# power_input_SCH1.net
KiCad netlist of a schematic drawn in Altium Designer
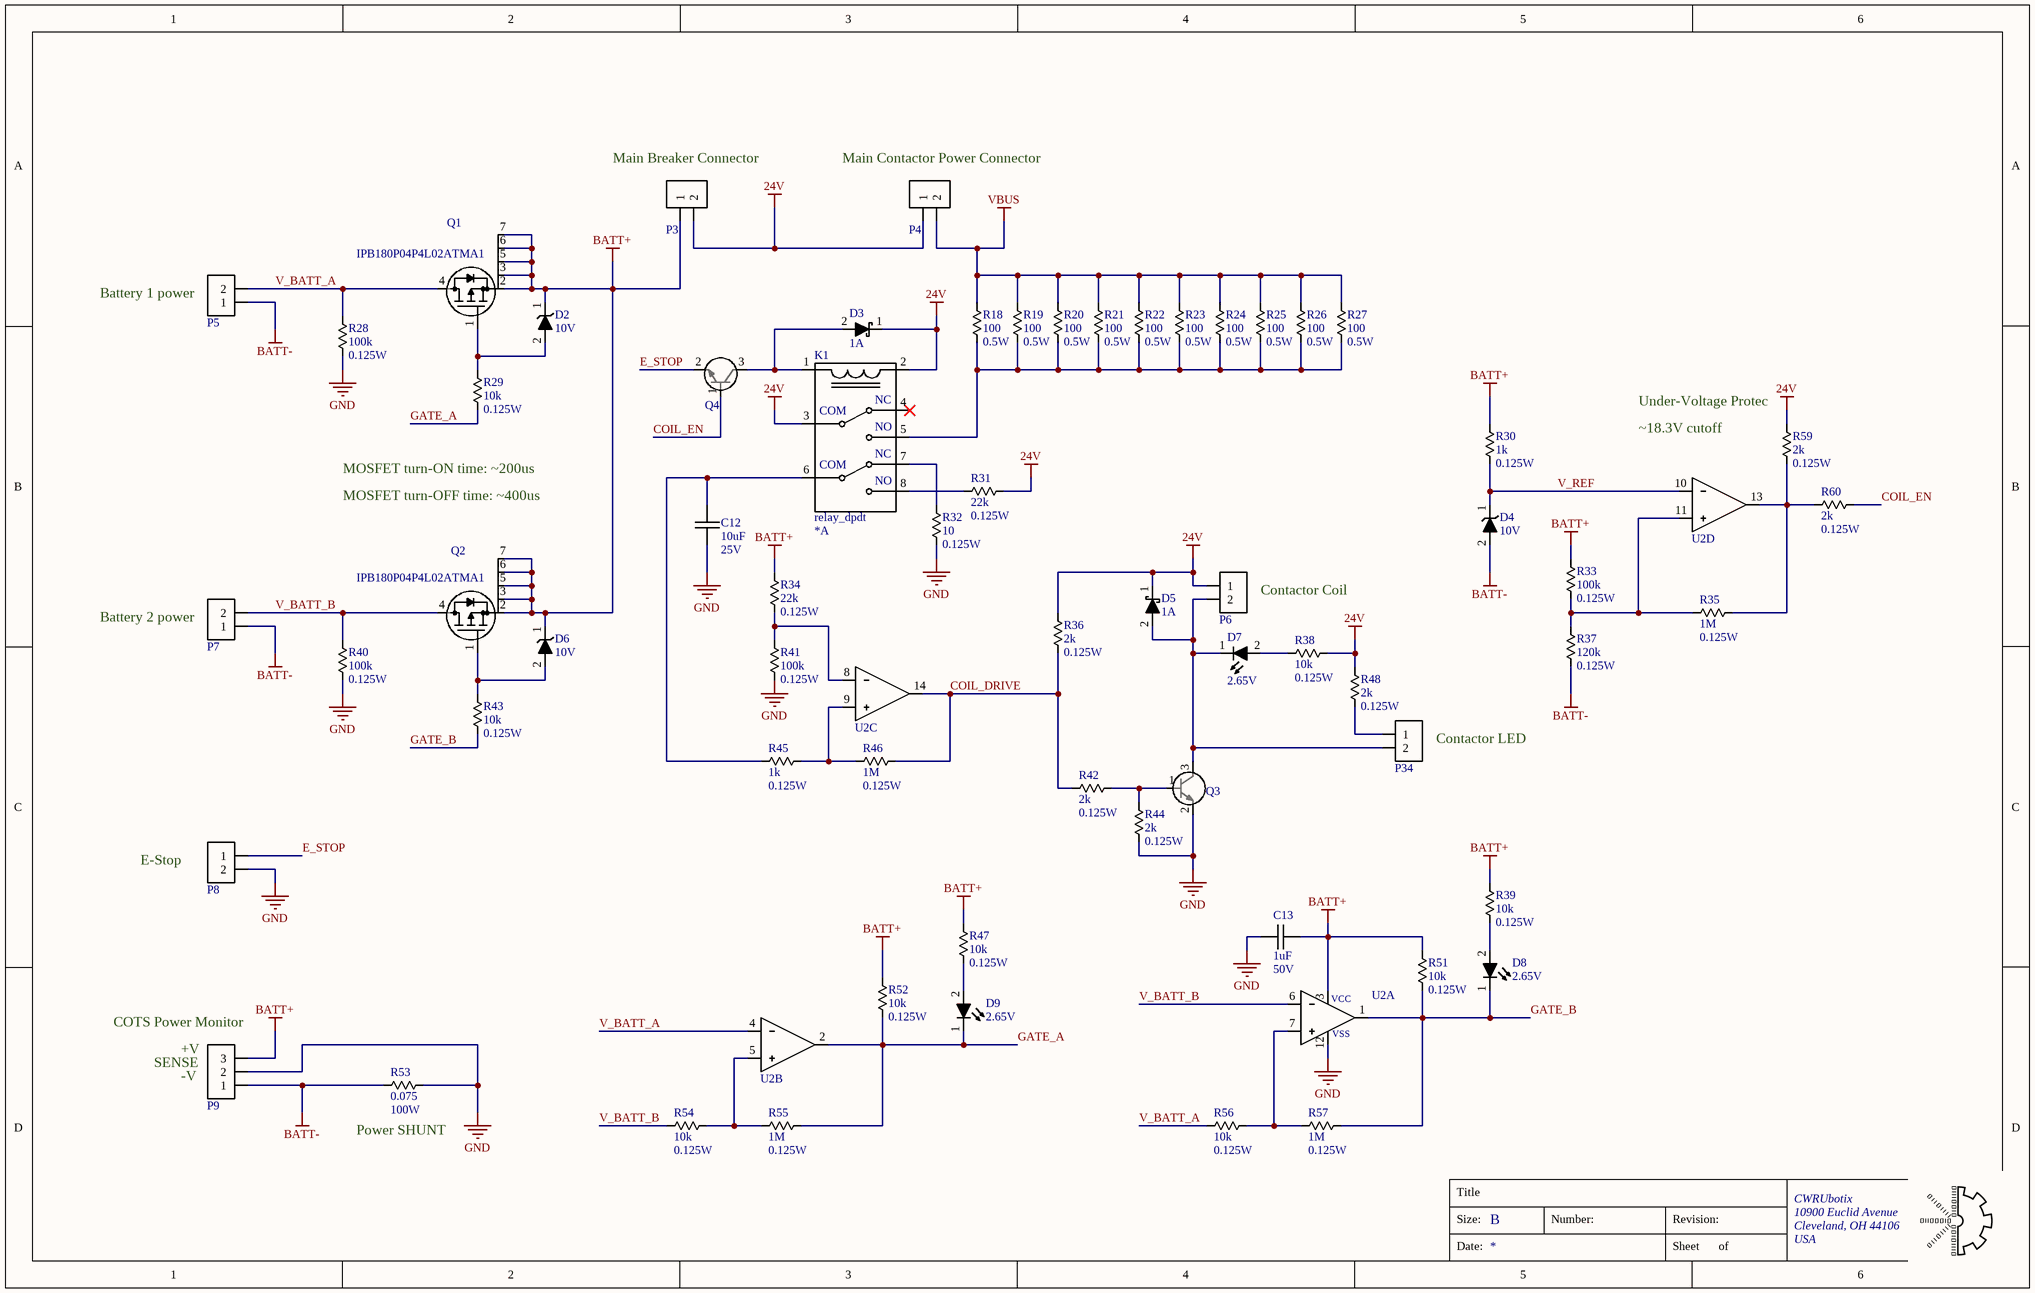
[diagram p0: power_input_SCH1.SchDoc]

(export (version "E")
  (design (tool "Eeschema 10.0.6"))
  (components
    (comp (ref "C12")
      (value "cap_single_np")
      (footprint "chip_1206")
      (description "CAP, 10uF, ±10%, 25V, X7R, 1206")
      (fields
        (field (name "TOLERANCE") "±10%")
        (field (name "CAPACITANCE") "10uF")
        (field (name "VOLTAGE RATING") "25V")
        (field (name "PART NUMBER") "CAP-00539")
      )
      (libsource (lib "Capacitors") (part "cap_single_np"))
    )
    (comp (ref "C13")
      (value "cap_single_np")
      (footprint "chip_0805")
      (description "CAP, 1uF, 10%, 50V, X7R, 0805")
      (fields
        (field (name "TOLERANCE") "10%")
        (field (name "CAPACITANCE") "1uF")
        (field (name "VOLTAGE RATING") "50V")
        (field (name "PART NUMBER") "CAP-00109")
      )
      (libsource (lib "Capacitors") (part "cap_single_np"))
    )
    (comp (ref "D2")
      (value "diode_1")
      (footprint "sod323_0")
      (description "Dio Zen, 10V, 2%, 200mW, SOD-323")
      (fields
        (field (name "REVERSE BREAKDOWN VOLTAGE") "10V")
        (field (name "PART NUMBER") "DIO-00019")
        (field (name "TOLERANCE") "2%")
      )
      (libsource (lib "Diodes") (part "diode_1"))
    )
    (comp (ref "D3")
      (value "diode_2")
      (footprint "sod123_0")
      (description "Dio Shtky, 1A, 0.55V, 40V, SOD-123")
      (fields
        (field (name "CURRENT RATING") "1A")
        (field (name "PART NUMBER") "DIO-00001")
        (field (name "MANUFACTURER") "ON Semi")
      )
      (libsource (lib "Diodes") (part "diode_2"))
    )
    (comp (ref "D4")
      (value "diode_1")
      (footprint "sod323_0")
      (description "Dio Zen, 10V, 2%, 200mW, SOD-323")
      (fields
        (field (name "REVERSE BREAKDOWN VOLTAGE") "10V")
        (field (name "PART NUMBER") "DIO-00019")
        (field (name "TOLERANCE") "2%")
      )
      (libsource (lib "Diodes") (part "diode_1"))
    )
    (comp (ref "D5")
      (value "diode_2")
      (footprint "sod123_0")
      (description "Dio Shtky, 1A, 0.55V, 40V, SOD-123")
      (fields
        (field (name "CURRENT RATING") "1A")
        (field (name "PART NUMBER") "DIO-00001")
        (field (name "MANUFACTURER") "ON Semi")
      )
      (libsource (lib "Diodes") (part "diode_2"))
    )
    (comp (ref "D6")
      (value "diode_1")
      (footprint "sod323_0")
      (description "Dio Zen, 10V, 2%, 200mW, SOD-323")
      (fields
        (field (name "REVERSE BREAKDOWN VOLTAGE") "10V")
        (field (name "PART NUMBER") "DIO-00019")
        (field (name "TOLERANCE") "2%")
      )
      (libsource (lib "Diodes") (part "diode_1"))
    )
    (comp (ref "D7")
      (value "diode_4")
      (footprint "chip_0603")
      (description "LED, Green, 0603, Low current, HELI2 Series")
      (fields
        (field (name "FORWARD VOLTAGE") "2.65V")
        (field (name "PART NUMBER") "DIO-00050")
        (field (name "MANUFACTURER") "Kingbright")
      )
      (libsource (lib "Diodes") (part "diode_4"))
    )
    (comp (ref "D8")
      (value "diode_4")
      (footprint "chip_0603")
      (description "LED, Green, 0603, Low current, HELI2 Series")
      (fields
        (field (name "FORWARD VOLTAGE") "2.65V")
        (field (name "PART NUMBER") "DIO-00050")
        (field (name "MANUFACTURER") "Kingbright")
      )
      (libsource (lib "Diodes") (part "diode_4"))
    )
    (comp (ref "D9")
      (value "diode_4")
      (footprint "chip_0603")
      (description "LED, Green, 0603, Low current, HELI2 Series")
      (fields
        (field (name "FORWARD VOLTAGE") "2.65V")
        (field (name "PART NUMBER") "DIO-00050")
        (field (name "MANUFACTURER") "Kingbright")
      )
      (libsource (lib "Diodes") (part "diode_4"))
    )
    (comp (ref "K1")
      (value "relay_dpdt")
      (footprint "RELAY_SHRACK_RT2")
      (description "Relay 24V, 8A, DPDT")
      (fields
        (field (name "CONTACT CURRENT RATING") "*A")
        (field (name "PART NUMBER") "MISC-00005")
        (field (name "MANUFACTURER") "TE Connectivity")
      )
      (libsource (lib "Misc") (part "relay_dpdt"))
    )
    (comp (ref "P3")
      (value "conn-2x1_0")
      (footprint "BARR_0.5IN_2x1_0")
      (description "Barrier Blk, 2 Pos, 50 A")
      (fields (field (name "PART NUMBER") "CONN-00001") (field (name "MANUFACTURER") "Molex"))
      (libsource (lib "Connectors") (part "conn-2x1_0"))
    )
    (comp (ref "P4")
      (value "conn-2x1_0")
      (footprint "BARR_0.5IN_2x1_0")
      (description "Barrier Blk, 2 Pos, 50 A")
      (fields (field (name "PART NUMBER") "CONN-00001") (field (name "MANUFACTURER") "Molex"))
      (libsource (lib "Connectors") (part "conn-2x1_0"))
    )
    (comp (ref "P5")
      (value "conn-2x1_0")
      (footprint "BARR_0.5IN_2x1_0")
      (description "Barrier Blk, 2 Pos, 50 A")
      (fields (field (name "PART NUMBER") "CONN-00001") (field (name "MANUFACTURER") "Molex"))
      (libsource (lib "Connectors") (part "conn-2x1_0"))
    )
    (comp (ref "P6")
      (value "conn-2x1_0")
      (footprint "JST_PHR_2_0")
      (description "JST PH 2x1, THT, 2.00mm Pitch")
      (fields (field (name "PART NUMBER") "CONN-00048") (field (name "MANUFACTURER") "JST"))
      (libsource (lib "Connectors") (part "conn-2x1_0"))
    )
    (comp (ref "P7")
      (value "conn-2x1_0")
      (footprint "BARR_0.5IN_2x1_0")
      (description "Barrier Blk, 2 Pos, 50 A")
      (fields (field (name "PART NUMBER") "CONN-00001") (field (name "MANUFACTURER") "Molex"))
      (libsource (lib "Connectors") (part "conn-2x1_0"))
    )
    (comp (ref "P8")
      (value "conn-2x1_0")
      (footprint "JST_PHR_2_0")
      (description "JST PH 2x1, THT, 2.00mm Pitch")
      (fields (field (name "PART NUMBER") "CONN-00048") (field (name "MANUFACTURER") "JST"))
      (libsource (lib "Connectors") (part "conn-2x1_0"))
    )
    (comp (ref "P9")
      (value "conn-3x1_0")
      (footprint "JST_PHR_3_0")
      (description "JST PH 3x1, THT, 2.00mm Pitch")
      (fields (field (name "PART NUMBER") "CONN-00047") (field (name "MANUFACTURER") "JST"))
      (libsource (lib "Connectors") (part "conn-3x1_0"))
    )
    (comp (ref "P34")
      (value "conn-2x1_0")
      (footprint "JST_PHR_2_0")
      (description "JST PH 2x1, THT, 2.00mm Pitch")
      (fields (field (name "PART NUMBER") "CONN-00048") (field (name "MANUFACTURER") "JST"))
      (libsource (lib "Connectors") (part "conn-2x1_0"))
    )
    (comp (ref "Q1")
      (value "p-mosfet_4")
      (footprint "PG-TO263-7-3")
      (description "XSTR PFET, 180A, 40V, Vgs 1.7V, PG-TO263-7-3")
      (fields
        (field (name "MANUFACTURER PN") "IPB180P04P4L02ATMA1")
        (field (name "PART NUMBER") "XSTR-00027")
        (field (name "MANUFACTURER") "Infineon")
      )
      (libsource (lib "Transistors") (part "p-mosfet_4"))
    )
    (comp (ref "Q2")
      (value "p-mosfet_4")
      (footprint "PG-TO263-7-3")
      (description "XSTR PFET, 180A, 40V, Vgs 1.7V, PG-TO263-7-3")
      (fields
        (field (name "MANUFACTURER PN") "IPB180P04P4L02ATMA1")
        (field (name "PART NUMBER") "XSTR-00027")
        (field (name "MANUFACTURER") "Infineon")
      )
      (libsource (lib "Transistors") (part "p-mosfet_4"))
    )
    (comp (ref "Q3")
      (value "npn-bjt_0")
      (footprint "sot-23-3")
      (description "XSTR NPN, 2A, 100V, Vce 0.15V, SOT-23")
      (fields (field (name "PART NUMBER") "XSTR-00021") (field (name "MANUFACTURER") "ON Semi"))
      (libsource (lib "Transistors") (part "npn-bjt_0"))
    )
    (comp (ref "Q4")
      (value "npn-bjt_0")
      (footprint "sot-23-3")
      (description "XSTR NPN, 2A, 100V, Vce 0.15V, SOT-23")
      (fields (field (name "PART NUMBER") "XSTR-00021") (field (name "MANUFACTURER") "ON Semi"))
      (libsource (lib "Transistors") (part "npn-bjt_0"))
    )
    (comp (ref "R18")
      (value "res_single")
      (footprint "chip_1206")
      (description "RES SMD 100 OHM 1% 1/2W 1206")
      (fields
        (field (name "TOLERANCE") "1%")
        (field (name "RESISTANCE") "100")
        (field (name "POWER RATING") "0.5W")
        (field (name "PART NUMBER") "RES-00595")
      )
      (libsource (lib "Resistors") (part "res_single"))
    )
    (comp (ref "R19")
      (value "res_single")
      (footprint "chip_1206")
      (description "RES SMD 100 OHM 1% 1/2W 1206")
      (fields
        (field (name "TOLERANCE") "1%")
        (field (name "RESISTANCE") "100")
        (field (name "POWER RATING") "0.5W")
        (field (name "PART NUMBER") "RES-00595")
      )
      (libsource (lib "Resistors") (part "res_single"))
    )
    (comp (ref "R20")
      (value "res_single")
      (footprint "chip_1206")
      (description "RES SMD 100 OHM 1% 1/2W 1206")
      (fields
        (field (name "TOLERANCE") "1%")
        (field (name "RESISTANCE") "100")
        (field (name "POWER RATING") "0.5W")
        (field (name "PART NUMBER") "RES-00595")
      )
      (libsource (lib "Resistors") (part "res_single"))
    )
    (comp (ref "R21")
      (value "res_single")
      (footprint "chip_1206")
      (description "RES SMD 100 OHM 1% 1/2W 1206")
      (fields
        (field (name "TOLERANCE") "1%")
        (field (name "RESISTANCE") "100")
        (field (name "POWER RATING") "0.5W")
        (field (name "PART NUMBER") "RES-00595")
      )
      (libsource (lib "Resistors") (part "res_single"))
    )
    (comp (ref "R22")
      (value "res_single")
      (footprint "chip_1206")
      (description "RES SMD 100 OHM 1% 1/2W 1206")
      (fields
        (field (name "TOLERANCE") "1%")
        (field (name "RESISTANCE") "100")
        (field (name "POWER RATING") "0.5W")
        (field (name "PART NUMBER") "RES-00595")
      )
      (libsource (lib "Resistors") (part "res_single"))
    )
    (comp (ref "R23")
      (value "res_single")
      (footprint "chip_1206")
      (description "RES SMD 100 OHM 1% 1/2W 1206")
      (fields
        (field (name "TOLERANCE") "1%")
        (field (name "RESISTANCE") "100")
        (field (name "POWER RATING") "0.5W")
        (field (name "PART NUMBER") "RES-00595")
      )
      (libsource (lib "Resistors") (part "res_single"))
    )
    (comp (ref "R24")
      (value "res_single")
      (footprint "chip_1206")
      (description "RES SMD 100 OHM 1% 1/2W 1206")
      (fields
        (field (name "TOLERANCE") "1%")
        (field (name "RESISTANCE") "100")
        (field (name "POWER RATING") "0.5W")
        (field (name "PART NUMBER") "RES-00595")
      )
      (libsource (lib "Resistors") (part "res_single"))
    )
    (comp (ref "R25")
      (value "res_single")
      (footprint "chip_1206")
      (description "RES SMD 100 OHM 1% 1/2W 1206")
      (fields
        (field (name "TOLERANCE") "1%")
        (field (name "RESISTANCE") "100")
        (field (name "POWER RATING") "0.5W")
        (field (name "PART NUMBER") "RES-00595")
      )
      (libsource (lib "Resistors") (part "res_single"))
    )
    (comp (ref "R26")
      (value "res_single")
      (footprint "chip_1206")
      (description "RES SMD 100 OHM 1% 1/2W 1206")
      (fields
        (field (name "TOLERANCE") "1%")
        (field (name "RESISTANCE") "100")
        (field (name "POWER RATING") "0.5W")
        (field (name "PART NUMBER") "RES-00595")
      )
      (libsource (lib "Resistors") (part "res_single"))
    )
    (comp (ref "R27")
      (value "res_single")
      (footprint "chip_1206")
      (description "RES SMD 100 OHM 1% 1/2W 1206")
      (fields
        (field (name "TOLERANCE") "1%")
        (field (name "RESISTANCE") "100")
        (field (name "POWER RATING") "0.5W")
        (field (name "PART NUMBER") "RES-00595")
      )
      (libsource (lib "Resistors") (part "res_single"))
    )
    (comp (ref "R28")
      (value "res_single")
      (footprint "chip_0805")
      (description "RES SMD 100K OHM 1% 1/8W 0805")
      (fields
        (field (name "TOLERANCE") "1%")
        (field (name "RESISTANCE") "100k")
        (field (name "POWER RATING") "0.125W")
        (field (name "PART NUMBER") "RES-00302")
      )
      (libsource (lib "Resistors") (part "res_single"))
    )
    (comp (ref "R29")
      (value "res_single")
      (footprint "chip_0805")
      (description "RES SMD 10K OHM 1% 1/8W 0805")
      (fields
        (field (name "TOLERANCE") "1%")
        (field (name "RESISTANCE") "10k")
        (field (name "POWER RATING") "0.125W")
        (field (name "PART NUMBER") "RES-00307")
      )
      (libsource (lib "Resistors") (part "res_single"))
    )
    (comp (ref "R30")
      (value "res_single")
      (footprint "chip_0805")
      (description "RES SMD 1K OHM 1% 1/8W 0805")
      (fields
        (field (name "TOLERANCE") "1%")
        (field (name "RESISTANCE") "1k")
        (field (name "POWER RATING") "0.125W")
        (field (name "PART NUMBER") "RES-00361")
      )
      (libsource (lib "Resistors") (part "res_single"))
    )
    (comp (ref "R31")
      (value "res_single")
      (footprint "chip_0805")
      (description "RES SMD 22K OHM 1% 1/8W 0805")
      (fields
        (field (name "TOLERANCE") "1%")
        (field (name "RESISTANCE") "22k")
        (field (name "POWER RATING") "0.125W")
        (field (name "PART NUMBER") "RES-00391")
      )
      (libsource (lib "Resistors") (part "res_single"))
    )
    (comp (ref "R32")
      (value "res_single")
      (footprint "chip_0805")
      (description "RES SMD 10 OHM 1% 1/8W 0805")
      (fields
        (field (name "TOLERANCE") "1%")
        (field (name "RESISTANCE") "10")
        (field (name "POWER RATING") "0.125W")
        (field (name "PART NUMBER") "RES-00117")
      )
      (libsource (lib "Resistors") (part "res_single"))
    )
    (comp (ref "R33")
      (value "res_single")
      (footprint "chip_0805")
      (description "RES SMD 100K OHM 1% 1/8W 0805")
      (fields
        (field (name "TOLERANCE") "1%")
        (field (name "RESISTANCE") "100k")
        (field (name "POWER RATING") "0.125W")
        (field (name "PART NUMBER") "RES-00302")
      )
      (libsource (lib "Resistors") (part "res_single"))
    )
    (comp (ref "R34")
      (value "res_single")
      (footprint "chip_0805")
      (description "RES SMD 22K OHM 1% 1/8W 0805")
      (fields
        (field (name "TOLERANCE") "1%")
        (field (name "RESISTANCE") "22k")
        (field (name "POWER RATING") "0.125W")
        (field (name "PART NUMBER") "RES-00391")
      )
      (libsource (lib "Resistors") (part "res_single"))
    )
    (comp (ref "R35")
      (value "res_single")
      (footprint "chip_0805")
      (description "RES SMD 1M OHM 1% 1/8W 0805")
      (fields
        (field (name "TOLERANCE") "1%")
        (field (name "RESISTANCE") "1M")
        (field (name "POWER RATING") "0.125W")
        (field (name "PART NUMBER") "RES-00363")
      )
      (libsource (lib "Resistors") (part "res_single"))
    )
    (comp (ref "R36")
      (value "res_single")
      (footprint "chip_0805")
      (description "RES SMD 2K OHM 1% 1/8W 0805")
      (fields
        (field (name "TOLERANCE") "1%")
        (field (name "RESISTANCE") "2k")
        (field (name "POWER RATING") "0.125W")
        (field (name "PART NUMBER") "RES-00414")
      )
      (libsource (lib "Resistors") (part "res_single"))
    )
    (comp (ref "R37")
      (value "res_single")
      (footprint "chip_0805")
      (description "RES SMD 120K OHM 1% 1/8W 0805")
      (fields
        (field (name "TOLERANCE") "1%")
        (field (name "RESISTANCE") "120k")
        (field (name "POWER RATING") "0.125W")
        (field (name "PART NUMBER") "RES-00319")
      )
      (libsource (lib "Resistors") (part "res_single"))
    )
    (comp (ref "R38")
      (value "res_single")
      (footprint "chip_0805")
      (description "RES SMD 10K OHM 1% 1/8W 0805")
      (fields
        (field (name "TOLERANCE") "1%")
        (field (name "RESISTANCE") "10k")
        (field (name "POWER RATING") "0.125W")
        (field (name "PART NUMBER") "RES-00307")
      )
      (libsource (lib "Resistors") (part "res_single"))
    )
    (comp (ref "R39")
      (value "res_single")
      (footprint "chip_0805")
      (description "RES SMD 10K OHM 1% 1/8W 0805")
      (fields
        (field (name "TOLERANCE") "1%")
        (field (name "RESISTANCE") "10k")
        (field (name "POWER RATING") "0.125W")
        (field (name "PART NUMBER") "RES-00307")
      )
      (libsource (lib "Resistors") (part "res_single"))
    )
    (comp (ref "R40")
      (value "res_single")
      (footprint "chip_0805")
      (description "RES SMD 100K OHM 1% 1/8W 0805")
      (fields
        (field (name "TOLERANCE") "1%")
        (field (name "RESISTANCE") "100k")
        (field (name "POWER RATING") "0.125W")
        (field (name "PART NUMBER") "RES-00302")
      )
      (libsource (lib "Resistors") (part "res_single"))
    )
    (comp (ref "R41")
      (value "res_single")
      (footprint "chip_0805")
      (description "RES SMD 100K OHM 1% 1/8W 0805")
      (fields
        (field (name "TOLERANCE") "1%")
        (field (name "RESISTANCE") "100k")
        (field (name "POWER RATING") "0.125W")
        (field (name "PART NUMBER") "RES-00302")
      )
      (libsource (lib "Resistors") (part "res_single"))
    )
    (comp (ref "R42")
      (value "res_single")
      (footprint "chip_0805")
      (description "RES SMD 2K OHM 1% 1/8W 0805")
      (fields
        (field (name "TOLERANCE") "1%")
        (field (name "RESISTANCE") "2k")
        (field (name "POWER RATING") "0.125W")
        (field (name "PART NUMBER") "RES-00414")
      )
      (libsource (lib "Resistors") (part "res_single"))
    )
    (comp (ref "R43")
      (value "res_single")
      (footprint "chip_0805")
      (description "RES SMD 10K OHM 1% 1/8W 0805")
      (fields
        (field (name "TOLERANCE") "1%")
        (field (name "RESISTANCE") "10k")
        (field (name "POWER RATING") "0.125W")
        (field (name "PART NUMBER") "RES-00307")
      )
      (libsource (lib "Resistors") (part "res_single"))
    )
    (comp (ref "R44")
      (value "res_single")
      (footprint "chip_0805")
      (description "RES SMD 2K OHM 1% 1/8W 0805")
      (fields
        (field (name "TOLERANCE") "1%")
        (field (name "RESISTANCE") "2k")
        (field (name "POWER RATING") "0.125W")
        (field (name "PART NUMBER") "RES-00414")
      )
      (libsource (lib "Resistors") (part "res_single"))
    )
    (comp (ref "R45")
      (value "res_single")
      (footprint "chip_0805")
      (description "RES SMD 1K OHM 1% 1/8W 0805")
      (fields
        (field (name "TOLERANCE") "1%")
        (field (name "RESISTANCE") "1k")
        (field (name "POWER RATING") "0.125W")
        (field (name "PART NUMBER") "RES-00361")
      )
      (libsource (lib "Resistors") (part "res_single"))
    )
    (comp (ref "R46")
      (value "res_single")
      (footprint "chip_0805")
      (description "RES SMD 1M OHM 1% 1/8W 0805")
      (fields
        (field (name "TOLERANCE") "1%")
        (field (name "RESISTANCE") "1M")
        (field (name "POWER RATING") "0.125W")
        (field (name "PART NUMBER") "RES-00363")
      )
      (libsource (lib "Resistors") (part "res_single"))
    )
    (comp (ref "R47")
      (value "res_single")
      (footprint "chip_0805")
      (description "RES SMD 10K OHM 1% 1/8W 0805")
      (fields
        (field (name "TOLERANCE") "1%")
        (field (name "RESISTANCE") "10k")
        (field (name "POWER RATING") "0.125W")
        (field (name "PART NUMBER") "RES-00307")
      )
      (libsource (lib "Resistors") (part "res_single"))
    )
    (comp (ref "R48")
      (value "res_single")
      (footprint "chip_0805")
      (description "RES SMD 2K OHM 1% 1/8W 0805")
      (fields
        (field (name "TOLERANCE") "1%")
        (field (name "RESISTANCE") "2k")
        (field (name "POWER RATING") "0.125W")
        (field (name "PART NUMBER") "RES-00414")
      )
      (libsource (lib "Resistors") (part "res_single"))
    )
    (comp (ref "R51")
      (value "res_single")
      (footprint "chip_0805")
      (description "RES SMD 10K OHM 1% 1/8W 0805")
      (fields
        (field (name "TOLERANCE") "1%")
        (field (name "RESISTANCE") "10k")
        (field (name "POWER RATING") "0.125W")
        (field (name "PART NUMBER") "RES-00307")
      )
      (libsource (lib "Resistors") (part "res_single"))
    )
    (comp (ref "R52")
      (value "res_single")
      (footprint "chip_0805")
      (description "RES SMD 10K OHM 1% 1/8W 0805")
      (fields
        (field (name "TOLERANCE") "1%")
        (field (name "RESISTANCE") "10k")
        (field (name "POWER RATING") "0.125W")
        (field (name "PART NUMBER") "RES-00307")
      )
      (libsource (lib "Resistors") (part "res_single"))
    )
    (comp (ref "R53")
      (value "res_single")
      (footprint "TO-247-2-H")
      (description "RES THT 0.075 OHM 1% 100W TO-247-2 Board Mounted")
      (fields
        (field (name "TOLERANCE") "1%")
        (field (name "RESISTANCE") "0.075")
        (field (name "POWER RATING") "100W")
        (field (name "PART NUMBER") "RES-00688")
      )
      (libsource (lib "Resistors") (part "res_single"))
    )
    (comp (ref "R54")
      (value "res_single")
      (footprint "chip_0805")
      (description "RES SMD 10K OHM 1% 1/8W 0805")
      (fields
        (field (name "TOLERANCE") "1%")
        (field (name "RESISTANCE") "10k")
        (field (name "POWER RATING") "0.125W")
        (field (name "PART NUMBER") "RES-00307")
      )
      (libsource (lib "Resistors") (part "res_single"))
    )
    (comp (ref "R55")
      (value "res_single")
      (footprint "chip_0805")
      (description "RES SMD 1M OHM 1% 1/8W 0805")
      (fields
        (field (name "TOLERANCE") "1%")
        (field (name "RESISTANCE") "1M")
        (field (name "POWER RATING") "0.125W")
        (field (name "PART NUMBER") "RES-00363")
      )
      (libsource (lib "Resistors") (part "res_single"))
    )
    (comp (ref "R56")
      (value "res_single")
      (footprint "chip_0805")
      (description "RES SMD 10K OHM 1% 1/8W 0805")
      (fields
        (field (name "TOLERANCE") "1%")
        (field (name "RESISTANCE") "10k")
        (field (name "POWER RATING") "0.125W")
        (field (name "PART NUMBER") "RES-00307")
      )
      (libsource (lib "Resistors") (part "res_single"))
    )
    (comp (ref "R57")
      (value "res_single")
      (footprint "chip_0805")
      (description "RES SMD 1M OHM 1% 1/8W 0805")
      (fields
        (field (name "TOLERANCE") "1%")
        (field (name "RESISTANCE") "1M")
        (field (name "POWER RATING") "0.125W")
        (field (name "PART NUMBER") "RES-00363")
      )
      (libsource (lib "Resistors") (part "res_single"))
    )
    (comp (ref "R59")
      (value "res_single")
      (footprint "chip_0805")
      (description "RES SMD 2K OHM 1% 1/8W 0805")
      (fields
        (field (name "TOLERANCE") "1%")
        (field (name "RESISTANCE") "2k")
        (field (name "POWER RATING") "0.125W")
        (field (name "PART NUMBER") "RES-00414")
      )
      (libsource (lib "Resistors") (part "res_single"))
    )
    (comp (ref "R60")
      (value "res_single")
      (footprint "chip_0805")
      (description "RES SMD 2K OHM 1% 1/8W 0805")
      (fields
        (field (name "TOLERANCE") "1%")
        (field (name "RESISTANCE") "2k")
        (field (name "POWER RATING") "0.125W")
        (field (name "PART NUMBER") "RES-00414")
      )
      (libsource (lib "Resistors") (part "res_single"))
    )
    (comp (ref "U2")
      (value "LM339")
      (footprint "so-14")
      (description "Comp, Quad, LM339")
      (fields (field (name "PART NUMBER") "ANLG-00006") (field (name "MANUFACTURER") "TI"))
      (libsource (lib "Analog") (part "LM339"))
    )
  )
  (nets
    (net (code "1") (name "/COIL_DRIVE") (class "Default")
      (node (ref "R36") (pin "1") (pinfunction "1_1") (pintype "passive"))
      (node (ref "R42") (pin "1") (pinfunction "1_1") (pintype "passive"))
      (node (ref "R46") (pin "2") (pinfunction "2_2") (pintype "passive"))
      (node (ref "U2") (pin "14") (pinfunction "14_14") (pintype "passive"))
    )
    (net (code "2") (name "/COIL_EN") (class "Default")
      (node (ref "Q4") (pin "1") (pinfunction "B_1") (pintype "passive"))
      (node (ref "R60") (pin "1") (pinfunction "1_1") (pintype "passive"))
    )
    (net (code "3") (name "/E_STOP") (class "Default")
      (node (ref "P8") (pin "1") (pinfunction "1_1") (pintype "passive"))
      (node (ref "Q4") (pin "2") (pinfunction "E_2") (pintype "passive"))
    )
    (net (code "4") (name "/GATE_A") (class "Default")
      (node (ref "D9") (pin "1") (pinfunction "1_1") (pintype "passive"))
      (node (ref "R29") (pin "2") (pinfunction "2_2") (pintype "passive"))
      (node (ref "R52") (pin "2") (pinfunction "2_2") (pintype "passive"))
      (node (ref "R55") (pin "2") (pinfunction "2_2") (pintype "passive"))
      (node (ref "U2") (pin "2") (pinfunction "2_2") (pintype "passive"))
    )
    (net (code "5") (name "/GATE_B") (class "Default")
      (node (ref "D8") (pin "1") (pinfunction "1_1") (pintype "passive"))
      (node (ref "R43") (pin "2") (pinfunction "2_2") (pintype "passive"))
      (node (ref "R51") (pin "2") (pinfunction "2_2") (pintype "passive"))
      (node (ref "R57") (pin "2") (pinfunction "2_2") (pintype "passive"))
      (node (ref "U2") (pin "1") (pinfunction "1_1") (pintype "passive"))
    )
    (net (code "6") (name "/V_BATT_A") (class "Default")
      (node (ref "P5") (pin "2") (pinfunction "2_2") (pintype "passive"))
      (node (ref "Q1") (pin "4") (pinfunction "D_4") (pintype "passive"))
      (node (ref "R28") (pin "2") (pinfunction "2_2") (pintype "passive"))
      (node (ref "R56") (pin "1") (pinfunction "1_1") (pintype "passive"))
      (node (ref "U2") (pin "4") (pinfunction "4_4") (pintype "passive"))
    )
    (net (code "7") (name "/V_BATT_B") (class "Default")
      (node (ref "P7") (pin "2") (pinfunction "2_2") (pintype "passive"))
      (node (ref "Q2") (pin "4") (pinfunction "D_4") (pintype "passive"))
      (node (ref "R40") (pin "1") (pinfunction "1_1") (pintype "passive"))
      (node (ref "R54") (pin "1") (pinfunction "1_1") (pintype "passive"))
      (node (ref "U2") (pin "6") (pinfunction "6_6") (pintype "passive"))
    )
    (net (code "8") (name "/V_REF") (class "Default")
      (node (ref "D4") (pin "1") (pinfunction "1_1") (pintype "passive"))
      (node (ref "R30") (pin "1") (pinfunction "1_1") (pintype "passive"))
      (node (ref "U2") (pin "10") (pinfunction "10_10") (pintype "passive"))
    )
    (net (code "9") (name "24V") (class "Default")
      (node (ref "D3") (pin "1") (pinfunction "1_1") (pintype "passive"))
      (node (ref "D5") (pin "1") (pinfunction "1_1") (pintype "passive"))
      (node (ref "K1") (pin "2") (pinfunction "2_2") (pintype "passive"))
      (node (ref "K1") (pin "3") (pinfunction "COM_3") (pintype "passive"))
      (node (ref "P3") (pin "2") (pinfunction "2_2") (pintype "passive"))
      (node (ref "P4") (pin "1") (pinfunction "1_1") (pintype "passive"))
      (node (ref "P6") (pin "1") (pinfunction "1_1") (pintype "passive"))
      (node (ref "R31") (pin "2") (pinfunction "2_2") (pintype "passive"))
      (node (ref "R36") (pin "2") (pinfunction "2_2") (pintype "passive"))
      (node (ref "R38") (pin "2") (pinfunction "2_2") (pintype "passive"))
      (node (ref "R48") (pin "2") (pinfunction "2_2") (pintype "passive"))
      (node (ref "R59") (pin "2") (pinfunction "2_2") (pintype "passive"))
    )
    (net (code "10") (name "BATT+") (class "Default")
      (node (ref "C13") (pin "2") (pinfunction "2_2") (pintype "passive"))
      (node (ref "D2") (pin "1") (pinfunction "1_1") (pintype "passive"))
      (node (ref "D6") (pin "1") (pinfunction "1_1") (pintype "passive"))
      (node (ref "P3") (pin "1") (pinfunction "1_1") (pintype "passive"))
      (node (ref "P9") (pin "3") (pinfunction "3_3") (pintype "passive"))
      (node (ref "Q1") (pin "2") (pinfunction "S_2") (pintype "passive"))
      (node (ref "Q1") (pin "3") (pinfunction "S_3") (pintype "passive"))
      (node (ref "Q1") (pin "5") (pinfunction "S_5") (pintype "passive"))
      (node (ref "Q1") (pin "6") (pinfunction "S_6") (pintype "passive"))
      (node (ref "Q1") (pin "7") (pinfunction "S_7") (pintype "passive"))
      (node (ref "Q2") (pin "2") (pinfunction "S_2") (pintype "passive"))
      (node (ref "Q2") (pin "3") (pinfunction "S_3") (pintype "passive"))
      (node (ref "Q2") (pin "5") (pinfunction "S_5") (pintype "passive"))
      (node (ref "Q2") (pin "6") (pinfunction "S_6") (pintype "passive"))
      (node (ref "Q2") (pin "7") (pinfunction "S_7") (pintype "passive"))
      (node (ref "R30") (pin "2") (pinfunction "2_2") (pintype "passive"))
      (node (ref "R33") (pin "1") (pinfunction "1_1") (pintype "passive"))
      (node (ref "R34") (pin "1") (pinfunction "1_1") (pintype "passive"))
      (node (ref "R39") (pin "1") (pinfunction "1_1") (pintype "passive"))
      (node (ref "R47") (pin "2") (pinfunction "2_2") (pintype "passive"))
      (node (ref "R51") (pin "1") (pinfunction "1_1") (pintype "passive"))
      (node (ref "R52") (pin "1") (pinfunction "1_1") (pintype "passive"))
      (node (ref "U2") (pin "3") (pinfunction "3_3") (pintype "passive"))
    )
    (net (code "11") (name "BATT-") (class "Default")
      (node (ref "D4") (pin "2") (pinfunction "2_2") (pintype "passive"))
      (node (ref "P5") (pin "1") (pinfunction "1_1") (pintype "passive"))
      (node (ref "P7") (pin "1") (pinfunction "1_1") (pintype "passive"))
      (node (ref "P9") (pin "1") (pinfunction "1_1") (pintype "passive"))
      (node (ref "R37") (pin "2") (pinfunction "2_2") (pintype "passive"))
      (node (ref "R53") (pin "1") (pinfunction "1_1") (pintype "passive"))
    )
    (net (code "12") (name "GND") (class "Default")
      (node (ref "C12") (pin "2") (pinfunction "2_2") (pintype "passive"))
      (node (ref "C13") (pin "1") (pinfunction "1_1") (pintype "passive"))
      (node (ref "P8") (pin "2") (pinfunction "2_2") (pintype "passive"))
      (node (ref "P9") (pin "2") (pinfunction "2_2") (pintype "passive"))
      (node (ref "Q3") (pin "2") (pinfunction "E_2") (pintype "passive"))
      (node (ref "R28") (pin "1") (pinfunction "1_1") (pintype "passive"))
      (node (ref "R32") (pin "2") (pinfunction "2_2") (pintype "passive"))
      (node (ref "R40") (pin "2") (pinfunction "2_2") (pintype "passive"))
      (node (ref "R41") (pin "2") (pinfunction "2_2") (pintype "passive"))
      (node (ref "R44") (pin "2") (pinfunction "2_2") (pintype "passive"))
      (node (ref "R53") (pin "2") (pinfunction "2_2") (pintype "passive"))
      (node (ref "U2") (pin "12") (pinfunction "12_12") (pintype "passive"))
    )
    (net (code "13") (name "Net-(C12-Pad1)") (class "Default")
      (node (ref "C12") (pin "1") (pinfunction "1_1") (pintype "passive"))
      (node (ref "K1") (pin "6") (pinfunction "COM_6") (pintype "passive"))
      (node (ref "R45") (pin "1") (pinfunction "1_1") (pintype "passive"))
    )
    (net (code "14") (name "Net-(D7-Pad2)") (class "Default")
      (node (ref "D7") (pin "2") (pinfunction "2_2") (pintype "passive"))
      (node (ref "R38") (pin "1") (pinfunction "1_1") (pintype "passive"))
    )
    (net (code "15") (name "Net-(D8-Pad2)") (class "Default")
      (node (ref "D8") (pin "2") (pinfunction "2_2") (pintype "passive"))
      (node (ref "R39") (pin "2") (pinfunction "2_2") (pintype "passive"))
    )
    (net (code "16") (name "Net-(D9-Pad2)") (class "Default")
      (node (ref "D9") (pin "2") (pinfunction "2_2") (pintype "passive"))
      (node (ref "R47") (pin "1") (pinfunction "1_1") (pintype "passive"))
    )
    (net (code "17") (name "Net-(K1-NC-Pad7)") (class "Default")
      (node (ref "K1") (pin "7") (pinfunction "NC_7") (pintype "passive"))
      (node (ref "R32") (pin "1") (pinfunction "1_1") (pintype "passive"))
    )
    (net (code "18") (name "Net-(K1-NO-Pad5)") (class "Default")
      (node (ref "K1") (pin "5") (pinfunction "NO_5") (pintype "passive"))
      (node (ref "R18") (pin "1") (pinfunction "1_1") (pintype "passive"))
      (node (ref "R19") (pin "1") (pinfunction "1_1") (pintype "passive"))
      (node (ref "R20") (pin "1") (pinfunction "1_1") (pintype "passive"))
      (node (ref "R21") (pin "1") (pinfunction "1_1") (pintype "passive"))
      (node (ref "R22") (pin "1") (pinfunction "1_1") (pintype "passive"))
      (node (ref "R23") (pin "1") (pinfunction "1_1") (pintype "passive"))
      (node (ref "R24") (pin "1") (pinfunction "1_1") (pintype "passive"))
      (node (ref "R25") (pin "1") (pinfunction "1_1") (pintype "passive"))
      (node (ref "R26") (pin "1") (pinfunction "1_1") (pintype "passive"))
      (node (ref "R27") (pin "1") (pinfunction "1_1") (pintype "passive"))
    )
    (net (code "19") (name "Net-(K1-NO-Pad8)") (class "Default")
      (node (ref "K1") (pin "8") (pinfunction "NO_8") (pintype "passive"))
      (node (ref "R31") (pin "1") (pinfunction "1_1") (pintype "passive"))
    )
    (net (code "20") (name "Net-(P34-Pad1)") (class "Default")
      (node (ref "P34") (pin "1") (pinfunction "1_1") (pintype "passive"))
      (node (ref "R48") (pin "1") (pinfunction "1_1") (pintype "passive"))
    )
    (net (code "21") (name "Net-(Q1-G)") (class "Default")
      (node (ref "D2") (pin "2") (pinfunction "2_2") (pintype "passive"))
      (node (ref "Q1") (pin "1") (pinfunction "G_1") (pintype "passive"))
      (node (ref "R29") (pin "1") (pinfunction "1_1") (pintype "passive"))
    )
    (net (code "22") (name "Net-(Q2-G)") (class "Default")
      (node (ref "D6") (pin "2") (pinfunction "2_2") (pintype "passive"))
      (node (ref "Q2") (pin "1") (pinfunction "G_1") (pintype "passive"))
      (node (ref "R43") (pin "1") (pinfunction "1_1") (pintype "passive"))
    )
    (net (code "23") (name "Net-(Q3-B)") (class "Default")
      (node (ref "Q3") (pin "1") (pinfunction "B_1") (pintype "passive"))
      (node (ref "R42") (pin "2") (pinfunction "2_2") (pintype "passive"))
      (node (ref "R44") (pin "1") (pinfunction "1_1") (pintype "passive"))
    )
    (net (code "24") (name "Net-(Q3-C)") (class "Default")
      (node (ref "D5") (pin "2") (pinfunction "2_2") (pintype "passive"))
      (node (ref "D7") (pin "1") (pinfunction "1_1") (pintype "passive"))
      (node (ref "P34") (pin "2") (pinfunction "2_2") (pintype "passive"))
      (node (ref "P6") (pin "2") (pinfunction "2_2") (pintype "passive"))
      (node (ref "Q3") (pin "3") (pinfunction "C_3") (pintype "passive"))
    )
    (net (code "25") (name "Net-(Q4-C)") (class "Default")
      (node (ref "D3") (pin "2") (pinfunction "2_2") (pintype "passive"))
      (node (ref "K1") (pin "1") (pinfunction "1_1") (pintype "passive"))
      (node (ref "Q4") (pin "3") (pinfunction "C_3") (pintype "passive"))
    )
    (net (code "26") (name "Net-(R33-Pad2)") (class "Default")
      (node (ref "R33") (pin "2") (pinfunction "2_2") (pintype "passive"))
      (node (ref "R35") (pin "1") (pinfunction "1_1") (pintype "passive"))
      (node (ref "R37") (pin "1") (pinfunction "1_1") (pintype "passive"))
      (node (ref "U2") (pin "11") (pinfunction "11_11") (pintype "passive"))
    )
    (net (code "27") (name "Net-(R34-Pad2)") (class "Default")
      (node (ref "R34") (pin "2") (pinfunction "2_2") (pintype "passive"))
      (node (ref "R41") (pin "1") (pinfunction "1_1") (pintype "passive"))
      (node (ref "U2") (pin "8") (pinfunction "8_8") (pintype "passive"))
    )
    (net (code "28") (name "Net-(R35-Pad2)") (class "Default")
      (node (ref "R35") (pin "2") (pinfunction "2_2") (pintype "passive"))
      (node (ref "R59") (pin "1") (pinfunction "1_1") (pintype "passive"))
      (node (ref "R60") (pin "2") (pinfunction "2_2") (pintype "passive"))
      (node (ref "U2") (pin "13") (pinfunction "13_13") (pintype "passive"))
    )
    (net (code "29") (name "Net-(R45-Pad2)") (class "Default")
      (node (ref "R45") (pin "2") (pinfunction "2_2") (pintype "passive"))
      (node (ref "R46") (pin "1") (pinfunction "1_1") (pintype "passive"))
      (node (ref "U2") (pin "9") (pinfunction "9_9") (pintype "passive"))
    )
    (net (code "30") (name "Net-(R54-Pad2)") (class "Default")
      (node (ref "R54") (pin "2") (pinfunction "2_2") (pintype "passive"))
      (node (ref "R55") (pin "1") (pinfunction "1_1") (pintype "passive"))
      (node (ref "U2") (pin "5") (pinfunction "5_5") (pintype "passive"))
    )
    (net (code "31") (name "Net-(R56-Pad2)") (class "Default")
      (node (ref "R56") (pin "2") (pinfunction "2_2") (pintype "passive"))
      (node (ref "R57") (pin "1") (pinfunction "1_1") (pintype "passive"))
      (node (ref "U2") (pin "7") (pinfunction "7_7") (pintype "passive"))
    )
    (net (code "32") (name "VBUS") (class "Default")
      (node (ref "P4") (pin "2") (pinfunction "2_2") (pintype "passive"))
      (node (ref "R18") (pin "2") (pinfunction "2_2") (pintype "passive"))
      (node (ref "R19") (pin "2") (pinfunction "2_2") (pintype "passive"))
      (node (ref "R20") (pin "2") (pinfunction "2_2") (pintype "passive"))
      (node (ref "R21") (pin "2") (pinfunction "2_2") (pintype "passive"))
      (node (ref "R22") (pin "2") (pinfunction "2_2") (pintype "passive"))
      (node (ref "R23") (pin "2") (pinfunction "2_2") (pintype "passive"))
      (node (ref "R24") (pin "2") (pinfunction "2_2") (pintype "passive"))
      (node (ref "R25") (pin "2") (pinfunction "2_2") (pintype "passive"))
      (node (ref "R26") (pin "2") (pinfunction "2_2") (pintype "passive"))
      (node (ref "R27") (pin "2") (pinfunction "2_2") (pintype "passive"))
    )
    (net (code "33") (name "unconnected-(K1-NC-Pad4)") (class "Default")
      (node (ref "K1") (pin "4") (pinfunction "NC_4") (pintype "passive+no_connect"))
    )
  )
)
